# battery_pack_protection.net
KiCad netlist of a schematic drawn in EAGLE
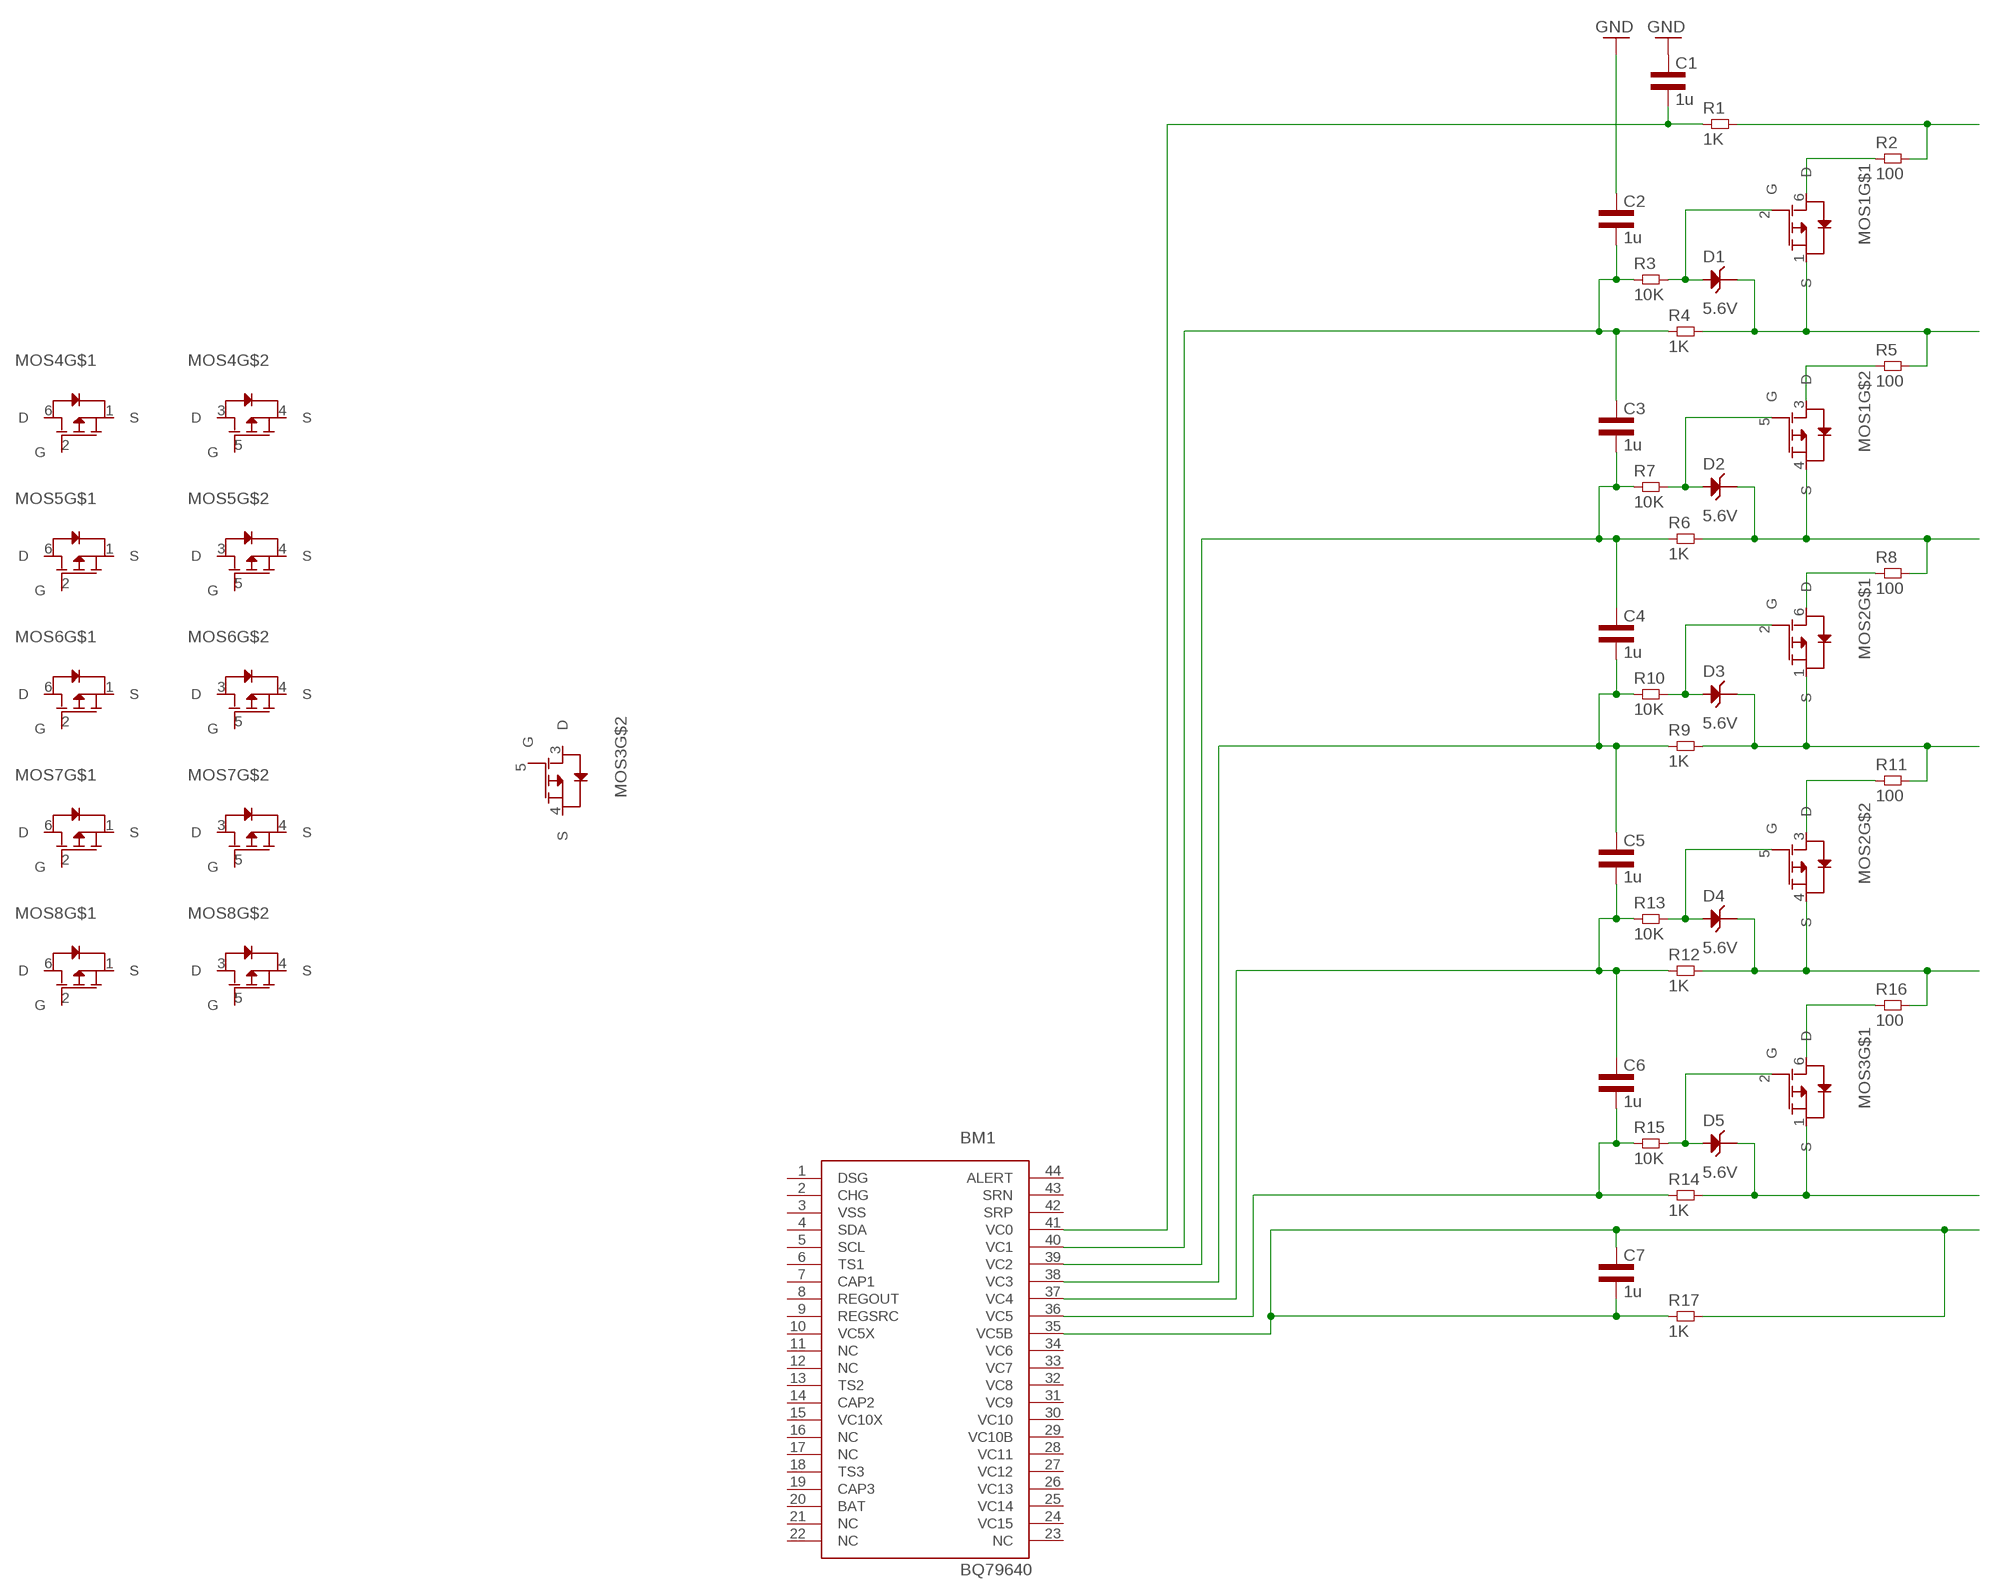
[diagram p0: schematic, sheet 1]
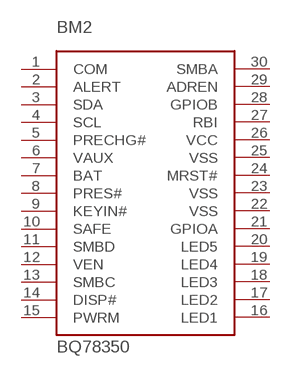
[diagram p1: schematic, sheet 2]

(export (version "E")
  (design (tool "Eeschema 10.0.6"))
  (components
    (comp (ref "BM2")
      (value "BQ78350")
      (footprint "eagle-import:R-PDSO-G30")
      (libsource (lib "eagle-import") (part "BQ78350"))
    )
    (comp (ref "BM1")
      (value "BQ76940")
      (footprint "eagle-import:R-PDSO-G44")
      (libsource (lib "eagle-import") (part "BQ76940"))
    )
    (comp (ref "C1")
      (value "1u")
      (footprint "eagle-import:0805L3")
      (libsource (lib "eagle-import") (part "CAP0805L3"))
    )
    (comp (ref "C2")
      (value "1u")
      (footprint "eagle-import:0805L3")
      (libsource (lib "eagle-import") (part "CAP0805L3"))
    )
    (comp (ref "C3")
      (value "1u")
      (footprint "eagle-import:0805L3")
      (libsource (lib "eagle-import") (part "CAP0805L3"))
    )
    (comp (ref "C4")
      (value "1u")
      (footprint "eagle-import:0805L3")
      (libsource (lib "eagle-import") (part "CAP0805L3"))
    )
    (comp (ref "C5")
      (value "1u")
      (footprint "eagle-import:0805L3")
      (libsource (lib "eagle-import") (part "CAP0805L3"))
    )
    (comp (ref "C6")
      (value "1u")
      (footprint "eagle-import:0805L3")
      (libsource (lib "eagle-import") (part "CAP0805L3"))
    )
    (comp (ref "C7")
      (value "1u")
      (footprint "eagle-import:0805L3")
      (libsource (lib "eagle-import") (part "CAP0805L3"))
    )
    (comp (ref "D1")
      (value "5.6V")
      (footprint "eagle-import:SOD323")
      (libsource (lib "eagle-import") (part "ZENERDIODESOD323"))
    )
    (comp (ref "D2")
      (value "5.6V")
      (footprint "eagle-import:SOD323")
      (libsource (lib "eagle-import") (part "ZENERDIODESOD323"))
    )
    (comp (ref "D3")
      (value "5.6V")
      (footprint "eagle-import:SOD323")
      (libsource (lib "eagle-import") (part "ZENERDIODESOD323"))
    )
    (comp (ref "D4")
      (value "5.6V")
      (footprint "eagle-import:SOD323")
      (libsource (lib "eagle-import") (part "ZENERDIODESOD323"))
    )
    (comp (ref "D5")
      (value "5.6V")
      (footprint "eagle-import:SOD323")
      (libsource (lib "eagle-import") (part "ZENERDIODESOD323"))
    )
    (comp (ref "MOS1")
      (value "FDY1002PZ")
      (footprint "eagle-import:SC89-6")
      (libsource (lib "eagle-import") (part "FDY1002PZ"))
    )
    (comp (ref "MOS2")
      (value "FDY1002PZ")
      (footprint "eagle-import:SC89-6")
      (libsource (lib "eagle-import") (part "FDY1002PZ"))
    )
    (comp (ref "MOS3")
      (value "FDY1002PZ")
      (footprint "eagle-import:SC89-6")
      (libsource (lib "eagle-import") (part "FDY1002PZ"))
    )
    (comp (ref "MOS4")
      (value "FDY1002PZ")
      (footprint "eagle-import:SC89-6")
      (libsource (lib "eagle-import") (part "FDY1002PZ"))
    )
    (comp (ref "MOS5")
      (value "FDY1002PZ")
      (footprint "eagle-import:SC89-6")
      (libsource (lib "eagle-import") (part "FDY1002PZ"))
    )
    (comp (ref "MOS6")
      (value "FDY1002PZ")
      (footprint "eagle-import:SC89-6")
      (libsource (lib "eagle-import") (part "FDY1002PZ"))
    )
    (comp (ref "MOS7")
      (value "FDY1002PZ")
      (footprint "eagle-import:SC89-6")
      (libsource (lib "eagle-import") (part "FDY1002PZ"))
    )
    (comp (ref "MOS8")
      (value "FDY1002PZ")
      (footprint "eagle-import:SC89-6")
      (libsource (lib "eagle-import") (part "FDY1002PZ"))
    )
    (comp (ref "R1")
      (value "1K")
      (footprint "eagle-import:0805L3")
      (libsource (lib "eagle-import") (part "RES0805L3"))
    )
    (comp (ref "R2")
      (value "100")
      (footprint "eagle-import:1206L3")
      (libsource (lib "eagle-import") (part "RES1206L3"))
    )
    (comp (ref "R3")
      (value "10K")
      (footprint "eagle-import:0805L3")
      (libsource (lib "eagle-import") (part "RES0805L3"))
    )
    (comp (ref "R4")
      (value "1K")
      (footprint "eagle-import:0805L3")
      (libsource (lib "eagle-import") (part "RES0805L3"))
    )
    (comp (ref "R5")
      (value "100")
      (footprint "eagle-import:1206L3")
      (libsource (lib "eagle-import") (part "RES1206L3"))
    )
    (comp (ref "R6")
      (value "1K")
      (footprint "eagle-import:0805L3")
      (libsource (lib "eagle-import") (part "RES0805L3"))
    )
    (comp (ref "R7")
      (value "10K")
      (footprint "eagle-import:0805L3")
      (libsource (lib "eagle-import") (part "RES0805L3"))
    )
    (comp (ref "R8")
      (value "100")
      (footprint "eagle-import:1206L3")
      (libsource (lib "eagle-import") (part "RES1206L3"))
    )
    (comp (ref "R9")
      (value "1K")
      (footprint "eagle-import:0805L3")
      (libsource (lib "eagle-import") (part "RES0805L3"))
    )
    (comp (ref "R10")
      (value "10K")
      (footprint "eagle-import:0805L3")
      (libsource (lib "eagle-import") (part "RES0805L3"))
    )
    (comp (ref "R11")
      (value "100")
      (footprint "eagle-import:1206L3")
      (libsource (lib "eagle-import") (part "RES1206L3"))
    )
    (comp (ref "R12")
      (value "1K")
      (footprint "eagle-import:0805L3")
      (libsource (lib "eagle-import") (part "RES0805L3"))
    )
    (comp (ref "R13")
      (value "10K")
      (footprint "eagle-import:0805L3")
      (libsource (lib "eagle-import") (part "RES0805L3"))
    )
    (comp (ref "R14")
      (value "1K")
      (footprint "eagle-import:0805L3")
      (libsource (lib "eagle-import") (part "RES0805L3"))
    )
    (comp (ref "R15")
      (value "10K")
      (footprint "eagle-import:0805L3")
      (libsource (lib "eagle-import") (part "RES0805L3"))
    )
    (comp (ref "R16")
      (value "100")
      (footprint "eagle-import:1206L3")
      (libsource (lib "eagle-import") (part "RES1206L3"))
    )
    (comp (ref "R17")
      (value "1K")
      (footprint "eagle-import:0805L3")
      (libsource (lib "eagle-import") (part "RES0805L3"))
    )
  )
  (nets
    (net (code "1") (name "GND") (class "Default")
      (node (ref "C1") (pin "1") (pinfunction "1_1") (pintype "bidirectional"))
      (node (ref "C2") (pin "1") (pinfunction "1_1") (pintype "bidirectional"))
    )
    (net (code "2") (name "Net-(BM1-VC0)") (class "Default")
      (node (ref "BM1") (pin "41") (pinfunction "VC0_41") (pintype "bidirectional"))
      (node (ref "C1") (pin "2") (pinfunction "2_2") (pintype "bidirectional"))
      (node (ref "R1") (pin "1") (pinfunction "1_1") (pintype "bidirectional"))
    )
    (net (code "3") (name "Net-(BM1-VC1)") (class "Default")
      (node (ref "BM1") (pin "40") (pinfunction "VC1_40") (pintype "bidirectional"))
      (node (ref "C2") (pin "2") (pinfunction "2_2") (pintype "bidirectional"))
      (node (ref "C3") (pin "1") (pinfunction "1_1") (pintype "bidirectional"))
      (node (ref "R3") (pin "1") (pinfunction "1_1") (pintype "bidirectional"))
      (node (ref "R4") (pin "1") (pinfunction "1_1") (pintype "bidirectional"))
    )
    (net (code "4") (name "Net-(BM1-VC2)") (class "Default")
      (node (ref "BM1") (pin "39") (pinfunction "VC2_39") (pintype "bidirectional"))
      (node (ref "C3") (pin "2") (pinfunction "2_2") (pintype "bidirectional"))
      (node (ref "C4") (pin "1") (pinfunction "1_1") (pintype "bidirectional"))
      (node (ref "R6") (pin "1") (pinfunction "1_1") (pintype "bidirectional"))
      (node (ref "R7") (pin "1") (pinfunction "1_1") (pintype "bidirectional"))
    )
    (net (code "5") (name "Net-(BM1-VC3)") (class "Default")
      (node (ref "BM1") (pin "38") (pinfunction "VC3_38") (pintype "bidirectional"))
      (node (ref "C4") (pin "2") (pinfunction "2_2") (pintype "bidirectional"))
      (node (ref "C5") (pin "1") (pinfunction "1_1") (pintype "bidirectional"))
      (node (ref "R10") (pin "1") (pinfunction "1_1") (pintype "bidirectional"))
      (node (ref "R9") (pin "1") (pinfunction "1_1") (pintype "bidirectional"))
    )
    (net (code "6") (name "Net-(BM1-VC4)") (class "Default")
      (node (ref "BM1") (pin "37") (pinfunction "VC4_37") (pintype "bidirectional"))
      (node (ref "C5") (pin "2") (pinfunction "2_2") (pintype "bidirectional"))
      (node (ref "C6") (pin "1") (pinfunction "1_1") (pintype "bidirectional"))
      (node (ref "R12") (pin "1") (pinfunction "1_1") (pintype "bidirectional"))
      (node (ref "R13") (pin "1") (pinfunction "1_1") (pintype "bidirectional"))
    )
    (net (code "7") (name "Net-(BM1-VC5)") (class "Default")
      (node (ref "BM1") (pin "36") (pinfunction "VC5_36") (pintype "bidirectional"))
      (node (ref "C6") (pin "2") (pinfunction "2_2") (pintype "bidirectional"))
      (node (ref "R14") (pin "1") (pinfunction "1_1") (pintype "bidirectional"))
      (node (ref "R15") (pin "1") (pinfunction "1_1") (pintype "bidirectional"))
    )
    (net (code "8") (name "Net-(BM1-VC5B)") (class "Default")
      (node (ref "BM1") (pin "35") (pinfunction "VC5B_35") (pintype "bidirectional"))
      (node (ref "C7") (pin "1") (pinfunction "1_1") (pintype "bidirectional"))
      (node (ref "C7") (pin "2") (pinfunction "2_2") (pintype "bidirectional"))
      (node (ref "R17") (pin "1") (pinfunction "1_1") (pintype "bidirectional"))
      (node (ref "R17") (pin "2") (pinfunction "2_2") (pintype "bidirectional"))
    )
    (net (code "9") (name "Net-(D1-ANODE)") (class "Default")
      (node (ref "D1") (pin "1") (pinfunction "ANODE_1") (pintype "bidirectional"))
      (node (ref "MOS1") (pin "2") (pinfunction "G_2") (pintype "bidirectional"))
      (node (ref "R3") (pin "2") (pinfunction "2_2") (pintype "bidirectional"))
    )
    (net (code "10") (name "Net-(D1-CATHODE)") (class "Default")
      (node (ref "D1") (pin "2") (pinfunction "CATHODE_2") (pintype "bidirectional"))
      (node (ref "MOS1") (pin "1") (pinfunction "S_1") (pintype "bidirectional"))
      (node (ref "R4") (pin "2") (pinfunction "2_2") (pintype "bidirectional"))
      (node (ref "R5") (pin "2") (pinfunction "2_2") (pintype "bidirectional"))
    )
    (net (code "11") (name "Net-(D2-ANODE)") (class "Default")
      (node (ref "D2") (pin "1") (pinfunction "ANODE_1") (pintype "bidirectional"))
      (node (ref "MOS1") (pin "5") (pinfunction "G_5") (pintype "bidirectional"))
      (node (ref "R7") (pin "2") (pinfunction "2_2") (pintype "bidirectional"))
    )
    (net (code "12") (name "Net-(D2-CATHODE)") (class "Default")
      (node (ref "D2") (pin "2") (pinfunction "CATHODE_2") (pintype "bidirectional"))
      (node (ref "MOS1") (pin "4") (pinfunction "S_4") (pintype "bidirectional"))
      (node (ref "R6") (pin "2") (pinfunction "2_2") (pintype "bidirectional"))
      (node (ref "R8") (pin "2") (pinfunction "2_2") (pintype "bidirectional"))
    )
    (net (code "13") (name "Net-(D3-ANODE)") (class "Default")
      (node (ref "D3") (pin "1") (pinfunction "ANODE_1") (pintype "bidirectional"))
      (node (ref "MOS2") (pin "2") (pinfunction "G_2") (pintype "bidirectional"))
      (node (ref "R10") (pin "2") (pinfunction "2_2") (pintype "bidirectional"))
    )
    (net (code "14") (name "Net-(D3-CATHODE)") (class "Default")
      (node (ref "D3") (pin "2") (pinfunction "CATHODE_2") (pintype "bidirectional"))
      (node (ref "MOS2") (pin "1") (pinfunction "S_1") (pintype "bidirectional"))
      (node (ref "R11") (pin "2") (pinfunction "2_2") (pintype "bidirectional"))
      (node (ref "R9") (pin "2") (pinfunction "2_2") (pintype "bidirectional"))
    )
    (net (code "15") (name "Net-(D4-ANODE)") (class "Default")
      (node (ref "D4") (pin "1") (pinfunction "ANODE_1") (pintype "bidirectional"))
      (node (ref "MOS2") (pin "5") (pinfunction "G_5") (pintype "bidirectional"))
      (node (ref "R13") (pin "2") (pinfunction "2_2") (pintype "bidirectional"))
    )
    (net (code "16") (name "Net-(D4-CATHODE)") (class "Default")
      (node (ref "D4") (pin "2") (pinfunction "CATHODE_2") (pintype "bidirectional"))
      (node (ref "MOS2") (pin "4") (pinfunction "S_4") (pintype "bidirectional"))
      (node (ref "R12") (pin "2") (pinfunction "2_2") (pintype "bidirectional"))
      (node (ref "R16") (pin "2") (pinfunction "2_2") (pintype "bidirectional"))
    )
    (net (code "17") (name "Net-(D5-ANODE)") (class "Default")
      (node (ref "D5") (pin "1") (pinfunction "ANODE_1") (pintype "bidirectional"))
      (node (ref "MOS3") (pin "2") (pinfunction "G_2") (pintype "bidirectional"))
      (node (ref "R15") (pin "2") (pinfunction "2_2") (pintype "bidirectional"))
    )
    (net (code "18") (name "Net-(D5-CATHODE)") (class "Default")
      (node (ref "D5") (pin "2") (pinfunction "CATHODE_2") (pintype "bidirectional"))
      (node (ref "MOS3") (pin "1") (pinfunction "S_1") (pintype "bidirectional"))
      (node (ref "R14") (pin "2") (pinfunction "2_2") (pintype "bidirectional"))
    )
    (net (code "19") (name "Net-(MOS1A-D)") (class "Default")
      (node (ref "MOS1") (pin "6") (pinfunction "D_6") (pintype "bidirectional"))
      (node (ref "R2") (pin "1") (pinfunction "1_1") (pintype "bidirectional"))
    )
    (net (code "20") (name "Net-(MOS1B-D)") (class "Default")
      (node (ref "MOS1") (pin "3") (pinfunction "D_3") (pintype "bidirectional"))
      (node (ref "R5") (pin "1") (pinfunction "1_1") (pintype "bidirectional"))
    )
    (net (code "21") (name "Net-(MOS2A-D)") (class "Default")
      (node (ref "MOS2") (pin "6") (pinfunction "D_6") (pintype "bidirectional"))
      (node (ref "R8") (pin "1") (pinfunction "1_1") (pintype "bidirectional"))
    )
    (net (code "22") (name "Net-(MOS2B-D)") (class "Default")
      (node (ref "MOS2") (pin "3") (pinfunction "D_3") (pintype "bidirectional"))
      (node (ref "R11") (pin "1") (pinfunction "1_1") (pintype "bidirectional"))
    )
    (net (code "23") (name "Net-(MOS3A-D)") (class "Default")
      (node (ref "MOS3") (pin "6") (pinfunction "D_6") (pintype "bidirectional"))
      (node (ref "R16") (pin "1") (pinfunction "1_1") (pintype "bidirectional"))
    )
    (net (code "24") (name "Net-(R1-Pad2)") (class "Default")
      (node (ref "R1") (pin "2") (pinfunction "2_2") (pintype "bidirectional"))
      (node (ref "R2") (pin "2") (pinfunction "2_2") (pintype "bidirectional"))
    )
    (net (code "25") (name "unconnected-(BM1-ALERT-Pad44)") (class "Default")
      (node (ref "BM1") (pin "44") (pinfunction "ALERT_44") (pintype "bidirectional"))
    )
    (net (code "26") (name "unconnected-(BM1-BAT-Pad20)") (class "Default")
      (node (ref "BM1") (pin "20") (pinfunction "BAT_20") (pintype "bidirectional"))
    )
    (net (code "27") (name "unconnected-(BM1-CAP1-Pad7)") (class "Default")
      (node (ref "BM1") (pin "7") (pinfunction "CAP1_7") (pintype "bidirectional"))
    )
    (net (code "28") (name "unconnected-(BM1-CAP2-Pad14)") (class "Default")
      (node (ref "BM1") (pin "14") (pinfunction "CAP2_14") (pintype "bidirectional"))
    )
    (net (code "29") (name "unconnected-(BM1-CAP3-Pad19)") (class "Default")
      (node (ref "BM1") (pin "19") (pinfunction "CAP3_19") (pintype "bidirectional"))
    )
    (net (code "30") (name "unconnected-(BM1-CHG-Pad2)") (class "Default")
      (node (ref "BM1") (pin "2") (pinfunction "CHG_2") (pintype "bidirectional"))
    )
    (net (code "31") (name "unconnected-(BM1-DSG-Pad1)") (class "Default")
      (node (ref "BM1") (pin "1") (pinfunction "DSG_1") (pintype "bidirectional"))
    )
    (net (code "32") (name "unconnected-(BM1-NC-Pad11)") (class "Default")
      (node (ref "BM1") (pin "11") (pinfunction "NC_11") (pintype "bidirectional"))
    )
    (net (code "33") (name "unconnected-(BM1-NC-Pad12)") (class "Default")
      (node (ref "BM1") (pin "12") (pinfunction "NC_12") (pintype "bidirectional"))
    )
    (net (code "34") (name "unconnected-(BM1-NC-Pad16)") (class "Default")
      (node (ref "BM1") (pin "16") (pinfunction "NC_16") (pintype "bidirectional"))
    )
    (net (code "35") (name "unconnected-(BM1-NC-Pad17)") (class "Default")
      (node (ref "BM1") (pin "17") (pinfunction "NC_17") (pintype "bidirectional"))
    )
    (net (code "36") (name "unconnected-(BM1-NC-Pad21)") (class "Default")
      (node (ref "BM1") (pin "21") (pinfunction "NC_21") (pintype "bidirectional"))
    )
    (net (code "37") (name "unconnected-(BM1-NC-Pad22)") (class "Default")
      (node (ref "BM1") (pin "22") (pinfunction "NC_22") (pintype "bidirectional"))
    )
    (net (code "38") (name "unconnected-(BM1-NC-Pad23)") (class "Default")
      (node (ref "BM1") (pin "23") (pinfunction "NC_23") (pintype "bidirectional"))
    )
    (net (code "39") (name "unconnected-(BM1-REGOUT-Pad8)") (class "Default")
      (node (ref "BM1") (pin "8") (pinfunction "REGOUT_8") (pintype "bidirectional"))
    )
    (net (code "40") (name "unconnected-(BM1-REGSRC-Pad9)") (class "Default")
      (node (ref "BM1") (pin "9") (pinfunction "REGSRC_9") (pintype "bidirectional"))
    )
    (net (code "41") (name "unconnected-(BM1-SCL-Pad5)") (class "Default")
      (node (ref "BM1") (pin "5") (pinfunction "SCL_5") (pintype "bidirectional"))
    )
    (net (code "42") (name "unconnected-(BM1-SDA-Pad4)") (class "Default")
      (node (ref "BM1") (pin "4") (pinfunction "SDA_4") (pintype "bidirectional"))
    )
    (net (code "43") (name "unconnected-(BM1-SRN-Pad43)") (class "Default")
      (node (ref "BM1") (pin "43") (pinfunction "SRN_43") (pintype "bidirectional"))
    )
    (net (code "44") (name "unconnected-(BM1-SRP-Pad42)") (class "Default")
      (node (ref "BM1") (pin "42") (pinfunction "SRP_42") (pintype "bidirectional"))
    )
    (net (code "45") (name "unconnected-(BM1-TS1-Pad6)") (class "Default")
      (node (ref "BM1") (pin "6") (pinfunction "TS1_6") (pintype "bidirectional"))
    )
    (net (code "46") (name "unconnected-(BM1-TS2-Pad13)") (class "Default")
      (node (ref "BM1") (pin "13") (pinfunction "TS2_13") (pintype "bidirectional"))
    )
    (net (code "47") (name "unconnected-(BM1-TS3-Pad18)") (class "Default")
      (node (ref "BM1") (pin "18") (pinfunction "TS3_18") (pintype "bidirectional"))
    )
    (net (code "48") (name "unconnected-(BM1-VC5X-Pad10)") (class "Default")
      (node (ref "BM1") (pin "10") (pinfunction "VC5X_10") (pintype "bidirectional"))
    )
    (net (code "49") (name "unconnected-(BM1-VC6-Pad34)") (class "Default")
      (node (ref "BM1") (pin "34") (pinfunction "VC6_34") (pintype "bidirectional"))
    )
    (net (code "50") (name "unconnected-(BM1-VC7-Pad33)") (class "Default")
      (node (ref "BM1") (pin "33") (pinfunction "VC7_33") (pintype "bidirectional"))
    )
    (net (code "51") (name "unconnected-(BM1-VC8-Pad32)") (class "Default")
      (node (ref "BM1") (pin "32") (pinfunction "VC8_32") (pintype "bidirectional"))
    )
    (net (code "52") (name "unconnected-(BM1-VC9-Pad31)") (class "Default")
      (node (ref "BM1") (pin "31") (pinfunction "VC9_31") (pintype "bidirectional"))
    )
    (net (code "53") (name "unconnected-(BM1-VC10-Pad30)") (class "Default")
      (node (ref "BM1") (pin "30") (pinfunction "VC10_30") (pintype "bidirectional"))
    )
    (net (code "54") (name "unconnected-(BM1-VC10B-Pad29)") (class "Default")
      (node (ref "BM1") (pin "29") (pinfunction "VC10B_29") (pintype "bidirectional"))
    )
    (net (code "55") (name "unconnected-(BM1-VC10X-Pad15)") (class "Default")
      (node (ref "BM1") (pin "15") (pinfunction "VC10X_15") (pintype "bidirectional"))
    )
    (net (code "56") (name "unconnected-(BM1-VC11-Pad28)") (class "Default")
      (node (ref "BM1") (pin "28") (pinfunction "VC11_28") (pintype "bidirectional"))
    )
    (net (code "57") (name "unconnected-(BM1-VC12-Pad27)") (class "Default")
      (node (ref "BM1") (pin "27") (pinfunction "VC12_27") (pintype "bidirectional"))
    )
    (net (code "58") (name "unconnected-(BM1-VC13-Pad26)") (class "Default")
      (node (ref "BM1") (pin "26") (pinfunction "VC13_26") (pintype "bidirectional"))
    )
    (net (code "59") (name "unconnected-(BM1-VC14-Pad25)") (class "Default")
      (node (ref "BM1") (pin "25") (pinfunction "VC14_25") (pintype "bidirectional"))
    )
    (net (code "60") (name "unconnected-(BM1-VC15-Pad24)") (class "Default")
      (node (ref "BM1") (pin "24") (pinfunction "VC15_24") (pintype "bidirectional"))
    )
    (net (code "61") (name "unconnected-(BM1-VSS-Pad3)") (class "Default")
      (node (ref "BM1") (pin "3") (pinfunction "VSS_3") (pintype "bidirectional"))
    )
    (net (code "62") (name "unconnected-(BM2-ADREN-Pad29)") (class "Default")
      (node (ref "BM2") (pin "29") (pinfunction "ADREN_29") (pintype "bidirectional"))
    )
    (net (code "63") (name "unconnected-(BM2-ALERT-Pad2)") (class "Default")
      (node (ref "BM2") (pin "2") (pinfunction "ALERT_2") (pintype "bidirectional"))
    )
    (net (code "64") (name "unconnected-(BM2-BAT-Pad7)") (class "Default")
      (node (ref "BM2") (pin "7") (pinfunction "BAT_7") (pintype "bidirectional"))
    )
    (net (code "65") (name "unconnected-(BM2-COM-Pad1)") (class "Default")
      (node (ref "BM2") (pin "1") (pinfunction "COM_1") (pintype "bidirectional"))
    )
    (net (code "66") (name "unconnected-(BM2-DISP#-Pad14)") (class "Default")
      (node (ref "BM2") (pin "14") (pinfunction "DISP#_14") (pintype "bidirectional"))
    )
    (net (code "67") (name "unconnected-(BM2-GPIOA-Pad21)") (class "Default")
      (node (ref "BM2") (pin "21") (pinfunction "GPIOA_21") (pintype "bidirectional"))
    )
    (net (code "68") (name "unconnected-(BM2-GPIOB-Pad28)") (class "Default")
      (node (ref "BM2") (pin "28") (pinfunction "GPIOB_28") (pintype "bidirectional"))
    )
    (net (code "69") (name "unconnected-(BM2-KEYIN#-Pad9)") (class "Default")
      (node (ref "BM2") (pin "9") (pinfunction "KEYIN#_9") (pintype "bidirectional"))
    )
    (net (code "70") (name "unconnected-(BM2-LED1-Pad16)") (class "Default")
      (node (ref "BM2") (pin "16") (pinfunction "LED1_16") (pintype "bidirectional"))
    )
    (net (code "71") (name "unconnected-(BM2-LED2-Pad17)") (class "Default")
      (node (ref "BM2") (pin "17") (pinfunction "LED2_17") (pintype "bidirectional"))
    )
    (net (code "72") (name "unconnected-(BM2-LED3-Pad18)") (class "Default")
      (node (ref "BM2") (pin "18") (pinfunction "LED3_18") (pintype "bidirectional"))
    )
    (net (code "73") (name "unconnected-(BM2-LED4-Pad19)") (class "Default")
      (node (ref "BM2") (pin "19") (pinfunction "LED4_19") (pintype "bidirectional"))
    )
    (net (code "74") (name "unconnected-(BM2-LED5-Pad20)") (class "Default")
      (node (ref "BM2") (pin "20") (pinfunction "LED5_20") (pintype "bidirectional"))
    )
    (net (code "75") (name "unconnected-(BM2-MRST#-Pad24)") (class "Default")
      (node (ref "BM2") (pin "24") (pinfunction "MRST#_24") (pintype "bidirectional"))
    )
    (net (code "76") (name "unconnected-(BM2-PRECHG#-Pad5)") (class "Default")
      (node (ref "BM2") (pin "5") (pinfunction "PRECHG#_5") (pintype "bidirectional"))
    )
    (net (code "77") (name "unconnected-(BM2-PRES#-Pad8)") (class "Default")
      (node (ref "BM2") (pin "8") (pinfunction "PRES#_8") (pintype "bidirectional"))
    )
    (net (code "78") (name "unconnected-(BM2-PWRM-Pad15)") (class "Default")
      (node (ref "BM2") (pin "15") (pinfunction "PWRM_15") (pintype "bidirectional"))
    )
    (net (code "79") (name "unconnected-(BM2-RBI-Pad27)") (class "Default")
      (node (ref "BM2") (pin "27") (pinfunction "RBI_27") (pintype "bidirectional"))
    )
    (net (code "80") (name "unconnected-(BM2-SAFE-Pad10)") (class "Default")
      (node (ref "BM2") (pin "10") (pinfunction "SAFE_10") (pintype "bidirectional"))
    )
    (net (code "81") (name "unconnected-(BM2-SCL-Pad4)") (class "Default")
      (node (ref "BM2") (pin "4") (pinfunction "SCL_4") (pintype "bidirectional"))
    )
    (net (code "82") (name "unconnected-(BM2-SDA-Pad3)") (class "Default")
      (node (ref "BM2") (pin "3") (pinfunction "SDA_3") (pintype "bidirectional"))
    )
    (net (code "83") (name "unconnected-(BM2-SMBA-Pad30)") (class "Default")
      (node (ref "BM2") (pin "30") (pinfunction "SMBA_30") (pintype "bidirectional"))
    )
    (net (code "84") (name "unconnected-(BM2-SMBC-Pad13)") (class "Default")
      (node (ref "BM2") (pin "13") (pinfunction "SMBC_13") (pintype "bidirectional"))
    )
    (net (code "85") (name "unconnected-(BM2-SMBD-Pad11)") (class "Default")
      (node (ref "BM2") (pin "11") (pinfunction "SMBD_11") (pintype "bidirectional"))
    )
    (net (code "86") (name "unconnected-(BM2-VAUX-Pad6)") (class "Default")
      (node (ref "BM2") (pin "6") (pinfunction "VAUX_6") (pintype "bidirectional"))
    )
    (net (code "87") (name "unconnected-(BM2-VCC-Pad26)") (class "Default")
      (node (ref "BM2") (pin "26") (pinfunction "VCC_26") (pintype "bidirectional"))
    )
    (net (code "88") (name "unconnected-(BM2-VEN-Pad12)") (class "Default")
      (node (ref "BM2") (pin "12") (pinfunction "VEN_12") (pintype "bidirectional"))
    )
    (net (code "89") (name "unconnected-(BM2-VSS-Pad22)") (class "Default")
      (node (ref "BM2") (pin "22") (pinfunction "VSS_22") (pintype "bidirectional"))
    )
    (net (code "90") (name "unconnected-(BM2-VSS-Pad23)") (class "Default")
      (node (ref "BM2") (pin "23") (pinfunction "VSS_23") (pintype "bidirectional"))
    )
    (net (code "91") (name "unconnected-(BM2-VSS-Pad25)") (class "Default")
      (node (ref "BM2") (pin "25") (pinfunction "VSS_25") (pintype "bidirectional"))
    )
    (net (code "92") (name "unconnected-(MOS3B-D-Pad3)") (class "Default")
      (node (ref "MOS3") (pin "3") (pinfunction "D_3") (pintype "bidirectional"))
    )
    (net (code "93") (name "unconnected-(MOS3B-G-Pad5)") (class "Default")
      (node (ref "MOS3") (pin "5") (pinfunction "G_5") (pintype "bidirectional"))
    )
    (net (code "94") (name "unconnected-(MOS3B-S-Pad4)") (class "Default")
      (node (ref "MOS3") (pin "4") (pinfunction "S_4") (pintype "bidirectional"))
    )
    (net (code "95") (name "unconnected-(MOS4A-D-Pad6)") (class "Default")
      (node (ref "MOS4") (pin "6") (pinfunction "D_6") (pintype "bidirectional"))
    )
    (net (code "96") (name "unconnected-(MOS4A-G-Pad2)") (class "Default")
      (node (ref "MOS4") (pin "2") (pinfunction "G_2") (pintype "bidirectional"))
    )
    (net (code "97") (name "unconnected-(MOS4A-S-Pad1)") (class "Default")
      (node (ref "MOS4") (pin "1") (pinfunction "S_1") (pintype "bidirectional"))
    )
    (net (code "98") (name "unconnected-(MOS4B-D-Pad3)") (class "Default")
      (node (ref "MOS4") (pin "3") (pinfunction "D_3") (pintype "bidirectional"))
    )
    (net (code "99") (name "unconnected-(MOS4B-G-Pad5)") (class "Default")
      (node (ref "MOS4") (pin "5") (pinfunction "G_5") (pintype "bidirectional"))
    )
    (net (code "100") (name "unconnected-(MOS4B-S-Pad4)") (class "Default")
      (node (ref "MOS4") (pin "4") (pinfunction "S_4") (pintype "bidirectional"))
    )
    (net (code "101") (name "unconnected-(MOS5A-D-Pad6)") (class "Default")
      (node (ref "MOS5") (pin "6") (pinfunction "D_6") (pintype "bidirectional"))
    )
    (net (code "102") (name "unconnected-(MOS5A-G-Pad2)") (class "Default")
      (node (ref "MOS5") (pin "2") (pinfunction "G_2") (pintype "bidirectional"))
    )
    (net (code "103") (name "unconnected-(MOS5A-S-Pad1)") (class "Default")
      (node (ref "MOS5") (pin "1") (pinfunction "S_1") (pintype "bidirectional"))
    )
    (net (code "104") (name "unconnected-(MOS5B-D-Pad3)") (class "Default")
      (node (ref "MOS5") (pin "3") (pinfunction "D_3") (pintype "bidirectional"))
    )
    (net (code "105") (name "unconnected-(MOS5B-G-Pad5)") (class "Default")
      (node (ref "MOS5") (pin "5") (pinfunction "G_5") (pintype "bidirectional"))
    )
    (net (code "106") (name "unconnected-(MOS5B-S-Pad4)") (class "Default")
      (node (ref "MOS5") (pin "4") (pinfunction "S_4") (pintype "bidirectional"))
    )
    (net (code "107") (name "unconnected-(MOS6A-D-Pad6)") (class "Default")
      (node (ref "MOS6") (pin "6") (pinfunction "D_6") (pintype "bidirectional"))
    )
    (net (code "108") (name "unconnected-(MOS6A-G-Pad2)") (class "Default")
      (node (ref "MOS6") (pin "2") (pinfunction "G_2") (pintype "bidirectional"))
    )
    (net (code "109") (name "unconnected-(MOS6A-S-Pad1)") (class "Default")
      (node (ref "MOS6") (pin "1") (pinfunction "S_1") (pintype "bidirectional"))
    )
    (net (code "110") (name "unconnected-(MOS6B-D-Pad3)") (class "Default")
      (node (ref "MOS6") (pin "3") (pinfunction "D_3") (pintype "bidirectional"))
    )
    (net (code "111") (name "unconnected-(MOS6B-G-Pad5)") (class "Default")
      (node (ref "MOS6") (pin "5") (pinfunction "G_5") (pintype "bidirectional"))
    )
    (net (code "112") (name "unconnected-(MOS6B-S-Pad4)") (class "Default")
      (node (ref "MOS6") (pin "4") (pinfunction "S_4") (pintype "bidirectional"))
    )
    (net (code "113") (name "unconnected-(MOS7A-D-Pad6)") (class "Default")
      (node (ref "MOS7") (pin "6") (pinfunction "D_6") (pintype "bidirectional"))
    )
    (net (code "114") (name "unconnected-(MOS7A-G-Pad2)") (class "Default")
      (node (ref "MOS7") (pin "2") (pinfunction "G_2") (pintype "bidirectional"))
    )
    (net (code "115") (name "unconnected-(MOS7A-S-Pad1)") (class "Default")
      (node (ref "MOS7") (pin "1") (pinfunction "S_1") (pintype "bidirectional"))
    )
    (net (code "116") (name "unconnected-(MOS7B-D-Pad3)") (class "Default")
      (node (ref "MOS7") (pin "3") (pinfunction "D_3") (pintype "bidirectional"))
    )
    (net (code "117") (name "unconnected-(MOS7B-G-Pad5)") (class "Default")
      (node (ref "MOS7") (pin "5") (pinfunction "G_5") (pintype "bidirectional"))
    )
    (net (code "118") (name "unconnected-(MOS7B-S-Pad4)") (class "Default")
      (node (ref "MOS7") (pin "4") (pinfunction "S_4") (pintype "bidirectional"))
    )
    (net (code "119") (name "unconnected-(MOS8A-D-Pad6)") (class "Default")
      (node (ref "MOS8") (pin "6") (pinfunction "D_6") (pintype "bidirectional"))
    )
    (net (code "120") (name "unconnected-(MOS8A-G-Pad2)") (class "Default")
      (node (ref "MOS8") (pin "2") (pinfunction "G_2") (pintype "bidirectional"))
    )
    (net (code "121") (name "unconnected-(MOS8A-S-Pad1)") (class "Default")
      (node (ref "MOS8") (pin "1") (pinfunction "S_1") (pintype "bidirectional"))
    )
    (net (code "122") (name "unconnected-(MOS8B-D-Pad3)") (class "Default")
      (node (ref "MOS8") (pin "3") (pinfunction "D_3") (pintype "bidirectional"))
    )
    (net (code "123") (name "unconnected-(MOS8B-G-Pad5)") (class "Default")
      (node (ref "MOS8") (pin "5") (pinfunction "G_5") (pintype "bidirectional"))
    )
    (net (code "124") (name "unconnected-(MOS8B-S-Pad4)") (class "Default")
      (node (ref "MOS8") (pin "4") (pinfunction "S_4") (pintype "bidirectional"))
    )
  )
)
